# SCH_Rover-Scheme1_2026-06-01.net
KiCad netlist of a schematic drawn in EasyEDA
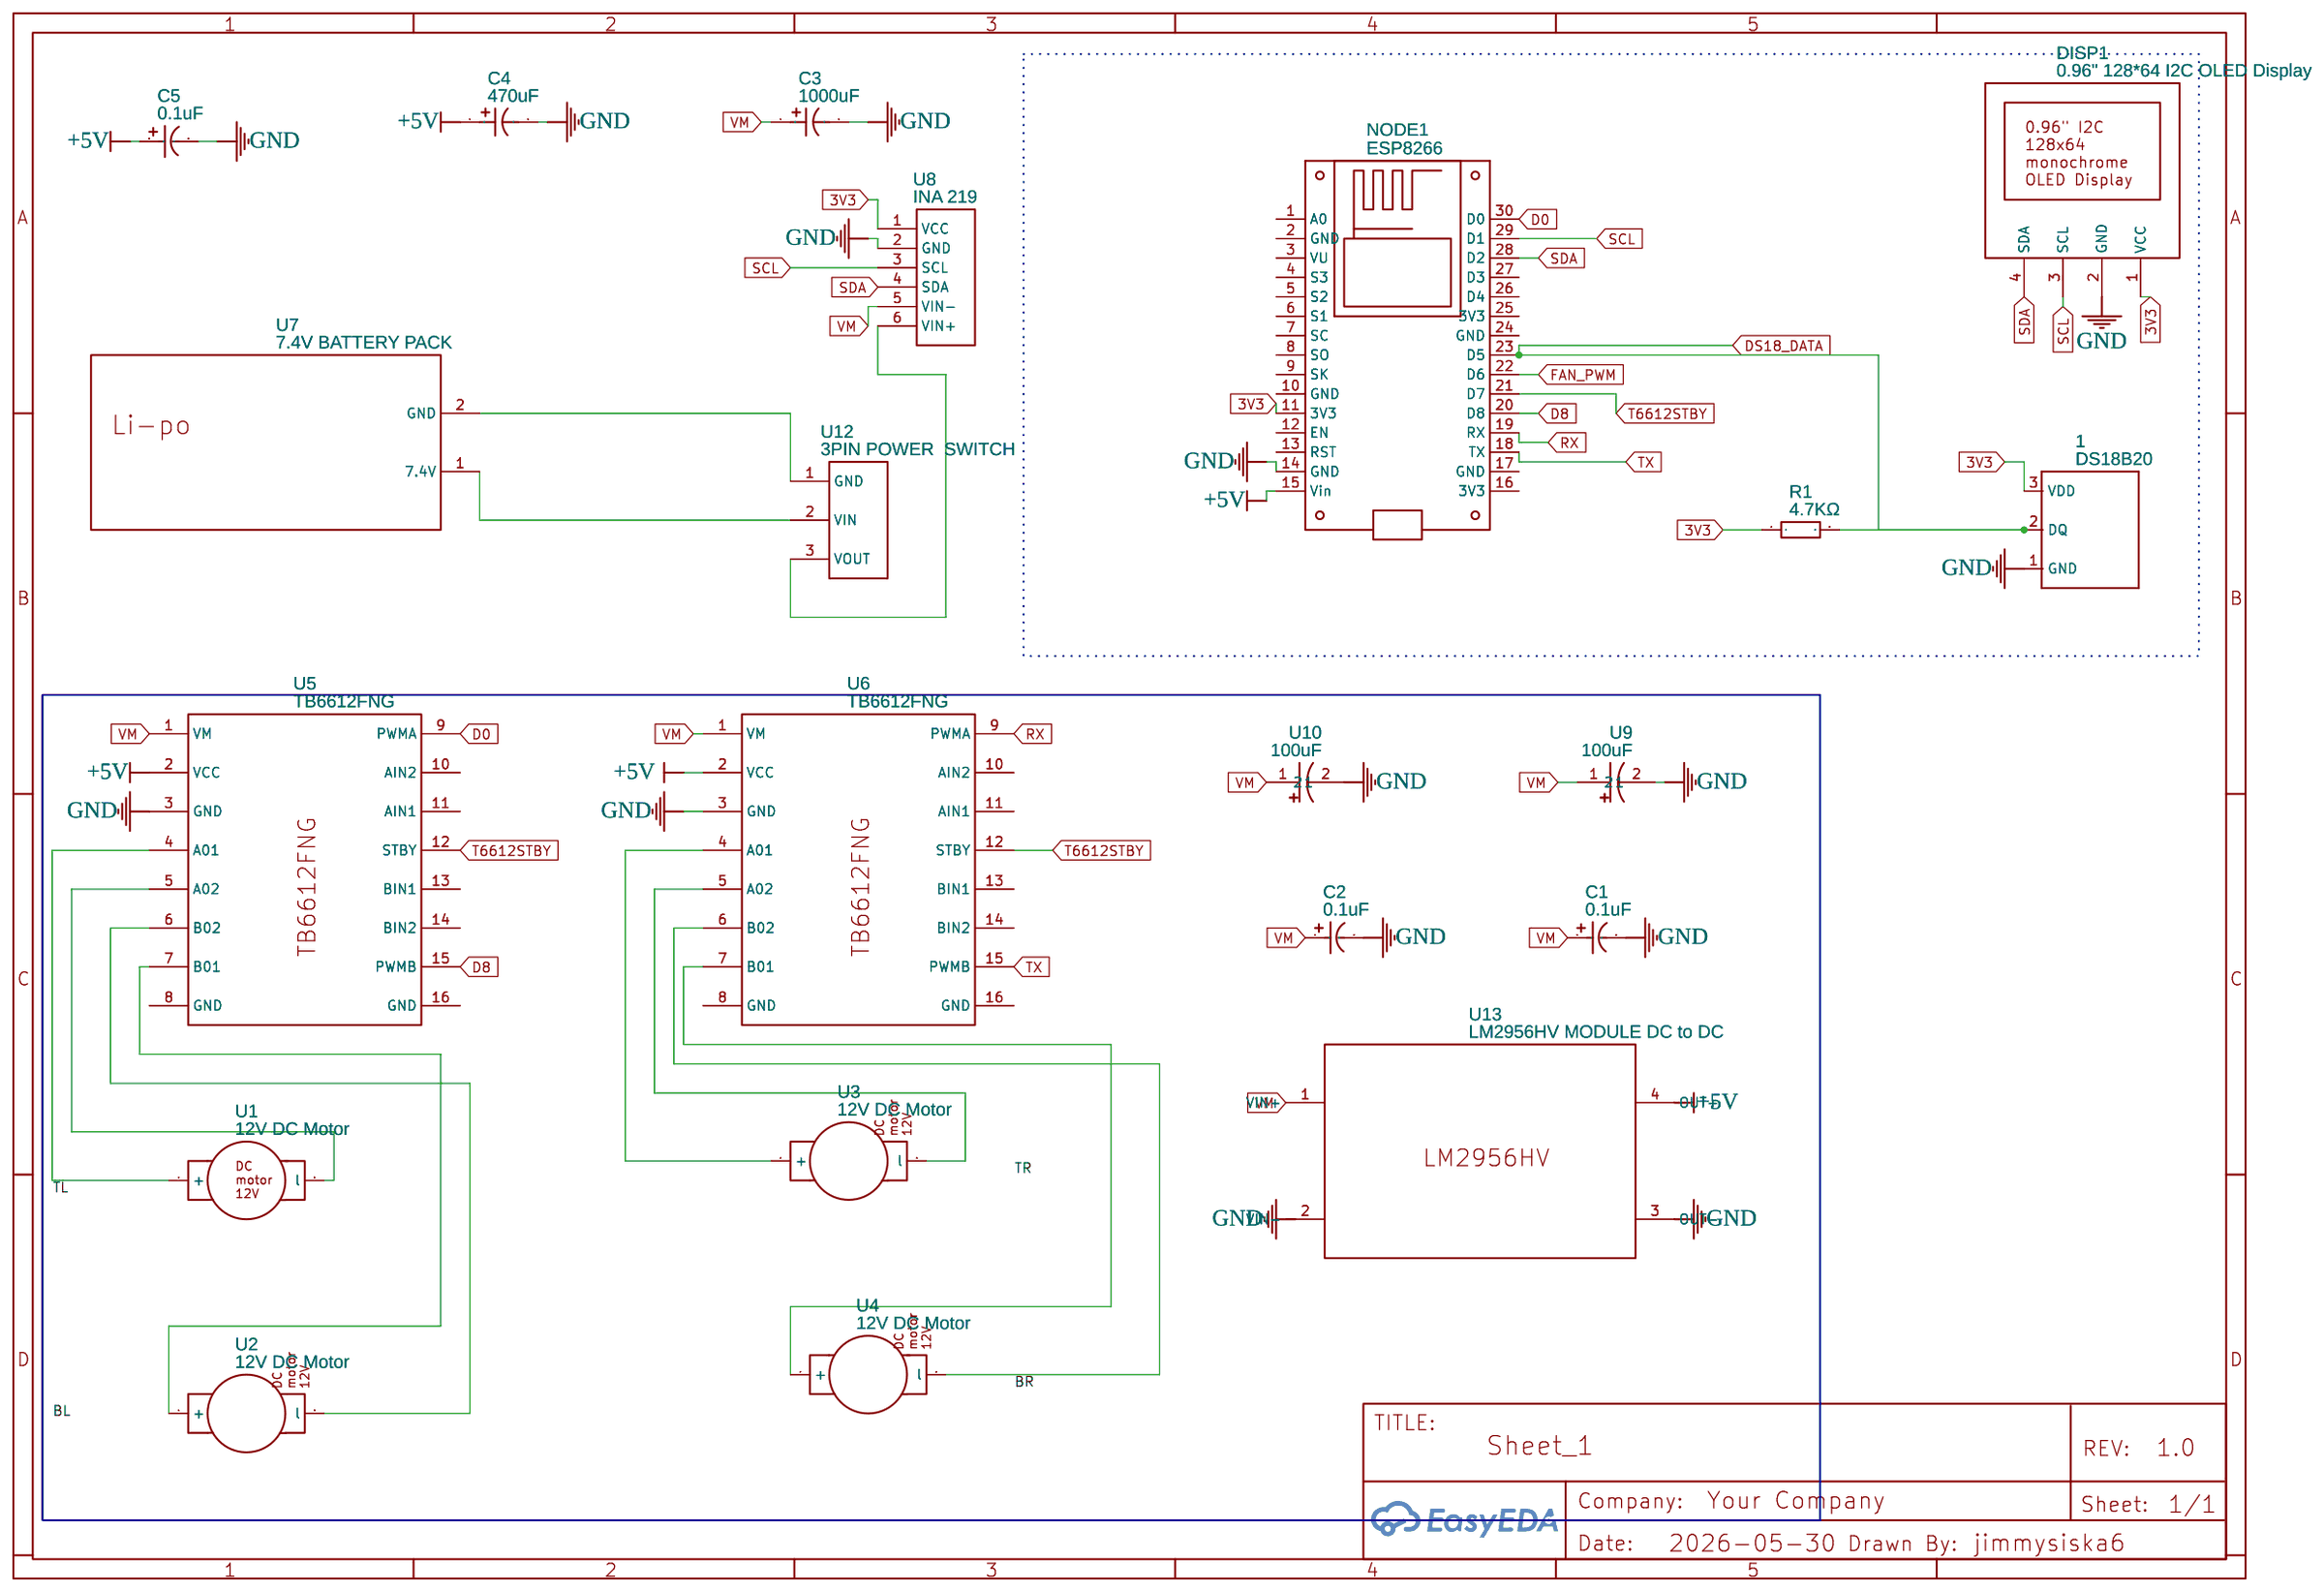
[diagram p0: schematic sheet]

(export (version "E")
  (design (tool "Eeschema 10.0.6"))
  (components
    (comp (ref "1") (value "DS18B20") (libsource (lib "") (part "DS18B20")))
    (comp (ref "C1") (value "0.1uF") (libsource (lib "") (part "0.1uF")))
    (comp (ref "C2") (value "0.1uF") (libsource (lib "") (part "0.1uF")))
    (comp (ref "C3")
      (value "1000uF")
      (fields
        (field (name "Manufacturer Part") "1000uF10V8x14GF")
        (field (name "Manufacturer") "Econd(米朗电子)")
      )
      (libsource (lib "") (part "1000UF10V8X14GF"))
    )
    (comp (ref "C4")
      (value "470uF")
      (fields (field (name "Manufacturer Part") "16V470uF CD288") (field (name "Manufacturer") "HRK(鸿瑞凯电子)"))
      (libsource (lib "") (part "16V470UF CD288"))
    )
    (comp (ref "C5") (value "0.1uF") (libsource (lib "") (part "0.1uF")))
    (comp (ref "DISP1")
      (value "0.96\" 128*64 I2C OLED Display")
      (libsource (lib "") (part "0.96{dblquote} 128*64 I2C OLED Display"))
    )
    (comp (ref "NODE1")
      (value "ESP8266")
      (fields (field (name "Manufacturer Part") "‎3-01-1841") (field (name "Manufacturer") "HiLetgo"))
      (libsource (lib "") (part "NODE MCU V3 ESP8266"))
    )
    (comp (ref "R1")
      (value "4.7KΩ")
      (fields (field (name "Manufacturer Part") "RC0402FR-074K7L") (field (name "Manufacturer") "Yageo"))
      (libsource (lib "") (part "4.7KΩ"))
    )
    (comp (ref "U1") (value "12V DC Motor") (libsource (lib "") (part "12V DC Motor_1")))
    (comp (ref "U2") (value "12V DC Motor") (libsource (lib "") (part "12V DC Motor")))
    (comp (ref "U3") (value "12V DC Motor") (libsource (lib "") (part "12V DC Motor")))
    (comp (ref "U4") (value "12V DC Motor") (libsource (lib "") (part "12V DC Motor")))
    (comp (ref "U5") (value "TB6612FNG") (libsource (lib "") (part "TB6612FNG")))
    (comp (ref "U6") (value "TB6612FNG") (libsource (lib "") (part "TB6612FNG")))
    (comp (ref "U7") (value "7.4V BATTERY PACK") (libsource (lib "") (part "7.2V BATTERY PACK")))
    (comp (ref "U8") (value "INA 219") (libsource (lib "") (part "INA 219")))
    (comp (ref "U9")
      (value "100uF")
      (fields
        (field (name "Manufacturer Part") "6.3NA100MEFC5X11")
        (field (name "Manufacturer") "rubycon(红宝石)")
      )
      (libsource (lib "") (part "100UF-D5XL11MM-HORN-TYPE-POLAR-ELECTROLYTIC-CAPACITORS COPY"))
    )
    (comp (ref "U10")
      (value "100uF")
      (fields
        (field (name "Manufacturer Part") "6.3NA100MEFC5X11")
        (field (name "Manufacturer") "rubycon(红宝石)")
      )
      (libsource (lib "") (part "100UF-D5XL11MM-HORN-TYPE-POLAR-ELECTROLYTIC-CAPACITORS COPY"))
    )
    (comp (ref "U12") (value "3PIN POWER  SWITCH") (libsource (lib "") (part "3PIN POWER  SWITCH")))
    (comp (ref "U13")
      (value "LM2956HV MODULE DC to DC")
      (libsource (lib "") (part "LM2956HV MODULE DC to DC"))
    )
  )
  (nets
    (net (code "1") (name "+5V") (class "Default")
      (node (ref "C4") (pin "1") (pinfunction "1_1") (pintype "input"))
      (node (ref "C5") (pin "1") (pinfunction "1_1") (pintype "input"))
      (node (ref "NODE1") (pin "15") (pinfunction "Vin_15") (pintype "unspecified"))
      (node (ref "U5") (pin "2") (pinfunction "VCC_2") (pintype "unspecified"))
      (node (ref "U6") (pin "2") (pinfunction "VCC_2") (pintype "unspecified"))
    )
    (net (code "6") (name "3V3") (class "Default")
      (node (ref "1") (pin "3") (pinfunction "VDD_3") (pintype "bidirectional"))
      (node (ref "DISP1") (pin "1") (pinfunction "VCC_1") (pintype "unspecified"))
      (node (ref "NODE1") (pin "11") (pinfunction "3V3_11") (pintype "unspecified"))
      (node (ref "R1") (pin "1") (pinfunction "1_1") (pintype "input"))
      (node (ref "U8") (pin "1") (pinfunction "VCC_1") (pintype "unspecified"))
    )
    (net (code "7") (name "D0") (class "Default")
      (node (ref "NODE1") (pin "30") (pinfunction "D0_30") (pintype "unspecified"))
      (node (ref "U5") (pin "9") (pinfunction "PWMA_9") (pintype "unspecified"))
    )
    (net (code "8") (name "D8") (class "Default")
      (node (ref "NODE1") (pin "20") (pinfunction "D8_20") (pintype "unspecified"))
      (node (ref "U5") (pin "15") (pinfunction "PWMB_15") (pintype "unspecified"))
    )
    (net (code "9") (name "DS18_DATA") (class "Default")
      (node (ref "1") (pin "2") (pinfunction "DQ_2") (pintype "bidirectional"))
      (node (ref "NODE1") (pin "23") (pinfunction "D5_23") (pintype "unspecified"))
      (node (ref "R1") (pin "2") (pinfunction "2_2") (pintype "input"))
    )
    (net (code "10") (name "FAN_PWM") (class "Default")
      (node (ref "NODE1") (pin "22") (pinfunction "D6_22") (pintype "unspecified"))
    )
    (net (code "11") (name "GND") (class "Default")
      (node (ref "1") (pin "1") (pinfunction "GND_1") (pintype "bidirectional"))
      (node (ref "C1") (pin "2") (pinfunction "2_2") (pintype "input"))
      (node (ref "C2") (pin "2") (pinfunction "2_2") (pintype "input"))
      (node (ref "C3") (pin "2") (pinfunction "2_2") (pintype "input"))
      (node (ref "C4") (pin "2") (pinfunction "2_2") (pintype "input"))
      (node (ref "C5") (pin "2") (pinfunction "2_2") (pintype "input"))
      (node (ref "DISP1") (pin "2") (pinfunction "GND_2") (pintype "unspecified"))
      (node (ref "NODE1") (pin "14") (pinfunction "GND_14") (pintype "unspecified"))
      (node (ref "U10") (pin "2") (pinfunction "2_2") (pintype "unspecified"))
      (node (ref "U5") (pin "3") (pinfunction "GND_3") (pintype "unspecified"))
      (node (ref "U6") (pin "3") (pinfunction "GND_3") (pintype "unspecified"))
      (node (ref "U8") (pin "2") (pinfunction "GND_2") (pintype "unspecified"))
      (node (ref "U9") (pin "2") (pinfunction "2_2") (pintype "unspecified"))
    )
    (net (code "12") (name "Net-(U1-+)") (class "Default")
      (node (ref "U1") (pin "1") (pinfunction "+_1") (pintype "unspecified"))
      (node (ref "U5") (pin "4") (pinfunction "A01_4") (pintype "unspecified"))
    )
    (net (code "13") (name "Net-(U1-l)") (class "Default")
      (node (ref "U1") (pin "2") (pinfunction "l_2") (pintype "unspecified"))
      (node (ref "U5") (pin "5") (pinfunction "A02_5") (pintype "unspecified"))
    )
    (net (code "14") (name "Net-(U2-+)") (class "Default")
      (node (ref "U2") (pin "1") (pinfunction "+_1") (pintype "unspecified"))
      (node (ref "U5") (pin "7") (pinfunction "B01_7") (pintype "unspecified"))
    )
    (net (code "15") (name "Net-(U2-l)") (class "Default")
      (node (ref "U2") (pin "2") (pinfunction "l_2") (pintype "unspecified"))
      (node (ref "U5") (pin "6") (pinfunction "B02_6") (pintype "unspecified"))
    )
    (net (code "16") (name "Net-(U3-+)") (class "Default")
      (node (ref "U3") (pin "1") (pinfunction "+_1") (pintype "unspecified"))
      (node (ref "U6") (pin "4") (pinfunction "A01_4") (pintype "unspecified"))
    )
    (net (code "17") (name "Net-(U3-l)") (class "Default")
      (node (ref "U3") (pin "2") (pinfunction "l_2") (pintype "unspecified"))
      (node (ref "U6") (pin "5") (pinfunction "A02_5") (pintype "unspecified"))
    )
    (net (code "18") (name "Net-(U4-+)") (class "Default")
      (node (ref "U4") (pin "1") (pinfunction "+_1") (pintype "unspecified"))
      (node (ref "U6") (pin "7") (pinfunction "B01_7") (pintype "unspecified"))
    )
    (net (code "19") (name "Net-(U4-l)") (class "Default")
      (node (ref "U4") (pin "2") (pinfunction "l_2") (pintype "unspecified"))
      (node (ref "U6") (pin "6") (pinfunction "B02_6") (pintype "unspecified"))
    )
    (net (code "20") (name "Net-(U12-GND)") (class "Default")
      (node (ref "U12") (pin "1") (pinfunction "GND_1") (pintype "unspecified"))
      (node (ref "U7") (pin "2") (pinfunction "GND_2") (pintype "unspecified"))
    )
    (net (code "21") (name "Net-(U12-VIN)") (class "Default")
      (node (ref "U12") (pin "2") (pinfunction "VIN_2") (pintype "unspecified"))
      (node (ref "U7") (pin "1") (pinfunction "7.4V_1") (pintype "passive"))
    )
    (net (code "22") (name "Net-(U12-VOUT)") (class "Default")
      (node (ref "U12") (pin "3") (pinfunction "VOUT_3") (pintype "unspecified"))
      (node (ref "U8") (pin "6") (pinfunction "VIN+_6") (pintype "unspecified"))
    )
    (net (code "23") (name "RX") (class "Default")
      (node (ref "NODE1") (pin "19") (pinfunction "RX_19") (pintype "unspecified"))
      (node (ref "U6") (pin "9") (pinfunction "PWMA_9") (pintype "unspecified"))
    )
    (net (code "24") (name "SCL") (class "Default")
      (node (ref "DISP1") (pin "3") (pinfunction "SCL_3") (pintype "unspecified"))
      (node (ref "NODE1") (pin "29") (pinfunction "D1_29") (pintype "unspecified"))
      (node (ref "U8") (pin "3") (pinfunction "SCL_3") (pintype "unspecified"))
    )
    (net (code "25") (name "SDA") (class "Default")
      (node (ref "DISP1") (pin "4") (pinfunction "SDA_4") (pintype "unspecified"))
      (node (ref "NODE1") (pin "28") (pinfunction "D2_28") (pintype "unspecified"))
      (node (ref "U8") (pin "4") (pinfunction "SDA_4") (pintype "unspecified"))
    )
    (net (code "26") (name "T6612STBY") (class "Default")
      (node (ref "NODE1") (pin "21") (pinfunction "D7_21") (pintype "unspecified"))
      (node (ref "U5") (pin "12") (pinfunction "STBY_12") (pintype "unspecified"))
      (node (ref "U6") (pin "12") (pinfunction "STBY_12") (pintype "unspecified"))
    )
    (net (code "27") (name "TX") (class "Default")
      (node (ref "NODE1") (pin "18") (pinfunction "TX_18") (pintype "unspecified"))
      (node (ref "U6") (pin "15") (pinfunction "PWMB_15") (pintype "unspecified"))
    )
    (net (code "28") (name "VM") (class "Default")
      (node (ref "C1") (pin "1") (pinfunction "1_1") (pintype "input"))
      (node (ref "C2") (pin "1") (pinfunction "1_1") (pintype "input"))
      (node (ref "C3") (pin "1") (pinfunction "1_1") (pintype "input"))
      (node (ref "U10") (pin "1") (pinfunction "1_1") (pintype "unspecified"))
      (node (ref "U5") (pin "1") (pinfunction "VM_1") (pintype "unspecified"))
      (node (ref "U6") (pin "1") (pinfunction "VM_1") (pintype "unspecified"))
      (node (ref "U8") (pin "5") (pinfunction "VIN-_5") (pintype "unspecified"))
      (node (ref "U9") (pin "1") (pinfunction "1_1") (pintype "unspecified"))
    )
    (net (code "29") (name "unconnected-(NODE1-3V3-Pad16)") (class "Default")
      (node (ref "NODE1") (pin "16") (pinfunction "3V3_16") (pintype "unspecified"))
    )
    (net (code "30") (name "unconnected-(NODE1-3V3-Pad25)") (class "Default")
      (node (ref "NODE1") (pin "25") (pinfunction "3V3_25") (pintype "unspecified"))
    )
    (net (code "31") (name "unconnected-(NODE1-A0-Pad1)") (class "Default")
      (node (ref "NODE1") (pin "1") (pinfunction "A0_1") (pintype "unspecified"))
    )
    (net (code "32") (name "unconnected-(NODE1-D3-Pad27)") (class "Default")
      (node (ref "NODE1") (pin "27") (pinfunction "D3_27") (pintype "unspecified"))
    )
    (net (code "33") (name "unconnected-(NODE1-D4-Pad26)") (class "Default")
      (node (ref "NODE1") (pin "26") (pinfunction "D4_26") (pintype "unspecified"))
    )
    (net (code "34") (name "unconnected-(NODE1-EN-Pad12)") (class "Default")
      (node (ref "NODE1") (pin "12") (pinfunction "EN_12") (pintype "unspecified"))
    )
    (net (code "35") (name "unconnected-(NODE1-GND-Pad2)") (class "Default")
      (node (ref "NODE1") (pin "2") (pinfunction "GND_2") (pintype "unspecified"))
    )
    (net (code "36") (name "unconnected-(NODE1-GND-Pad10)") (class "Default")
      (node (ref "NODE1") (pin "10") (pinfunction "GND_10") (pintype "unspecified"))
    )
    (net (code "37") (name "unconnected-(NODE1-GND-Pad17)") (class "Default")
      (node (ref "NODE1") (pin "17") (pinfunction "GND_17") (pintype "unspecified"))
    )
    (net (code "38") (name "unconnected-(NODE1-GND-Pad24)") (class "Default")
      (node (ref "NODE1") (pin "24") (pinfunction "GND_24") (pintype "unspecified"))
    )
    (net (code "39") (name "unconnected-(NODE1-RST-Pad13)") (class "Default")
      (node (ref "NODE1") (pin "13") (pinfunction "RST_13") (pintype "unspecified"))
    )
    (net (code "40") (name "unconnected-(NODE1-S1-Pad6)") (class "Default")
      (node (ref "NODE1") (pin "6") (pinfunction "S1_6") (pintype "unspecified"))
    )
    (net (code "41") (name "unconnected-(NODE1-S2-Pad5)") (class "Default")
      (node (ref "NODE1") (pin "5") (pinfunction "S2_5") (pintype "unspecified"))
    )
    (net (code "42") (name "unconnected-(NODE1-S3-Pad4)") (class "Default")
      (node (ref "NODE1") (pin "4") (pinfunction "S3_4") (pintype "unspecified"))
    )
    (net (code "43") (name "unconnected-(NODE1-SC-Pad7)") (class "Default")
      (node (ref "NODE1") (pin "7") (pinfunction "SC_7") (pintype "unspecified"))
    )
    (net (code "44") (name "unconnected-(NODE1-SK-Pad9)") (class "Default")
      (node (ref "NODE1") (pin "9") (pinfunction "SK_9") (pintype "unspecified"))
    )
    (net (code "45") (name "unconnected-(NODE1-SO-Pad8)") (class "Default")
      (node (ref "NODE1") (pin "8") (pinfunction "SO_8") (pintype "unspecified"))
    )
    (net (code "46") (name "unconnected-(NODE1-VU-Pad3)") (class "Default")
      (node (ref "NODE1") (pin "3") (pinfunction "VU_3") (pintype "unspecified"))
    )
    (net (code "47") (name "unconnected-(U5-AIN1-Pad11)") (class "Default")
      (node (ref "U5") (pin "11") (pinfunction "AIN1_11") (pintype "unspecified"))
    )
    (net (code "48") (name "unconnected-(U5-AIN2-Pad10)") (class "Default")
      (node (ref "U5") (pin "10") (pinfunction "AIN2_10") (pintype "unspecified"))
    )
    (net (code "49") (name "unconnected-(U5-BIN1-Pad13)") (class "Default")
      (node (ref "U5") (pin "13") (pinfunction "BIN1_13") (pintype "unspecified"))
    )
    (net (code "50") (name "unconnected-(U5-BIN2-Pad14)") (class "Default")
      (node (ref "U5") (pin "14") (pinfunction "BIN2_14") (pintype "unspecified"))
    )
    (net (code "51") (name "unconnected-(U5-GND-Pad8)") (class "Default")
      (node (ref "U5") (pin "8") (pinfunction "GND_8") (pintype "unspecified"))
    )
    (net (code "52") (name "unconnected-(U5-GND-Pad16)") (class "Default")
      (node (ref "U5") (pin "16") (pinfunction "GND_16") (pintype "unspecified"))
    )
    (net (code "53") (name "unconnected-(U6-AIN1-Pad11)") (class "Default")
      (node (ref "U6") (pin "11") (pinfunction "AIN1_11") (pintype "unspecified"))
    )
    (net (code "54") (name "unconnected-(U6-AIN2-Pad10)") (class "Default")
      (node (ref "U6") (pin "10") (pinfunction "AIN2_10") (pintype "unspecified"))
    )
    (net (code "55") (name "unconnected-(U6-BIN1-Pad13)") (class "Default")
      (node (ref "U6") (pin "13") (pinfunction "BIN1_13") (pintype "unspecified"))
    )
    (net (code "56") (name "unconnected-(U6-BIN2-Pad14)") (class "Default")
      (node (ref "U6") (pin "14") (pinfunction "BIN2_14") (pintype "unspecified"))
    )
    (net (code "57") (name "unconnected-(U6-GND-Pad8)") (class "Default")
      (node (ref "U6") (pin "8") (pinfunction "GND_8") (pintype "unspecified"))
    )
    (net (code "58") (name "unconnected-(U6-GND-Pad16)") (class "Default")
      (node (ref "U6") (pin "16") (pinfunction "GND_16") (pintype "unspecified"))
    )
    (net (code "59") (name "unconnected-(U13-OUT+-Pad4)") (class "Default")
      (node (ref "U13") (pin "4") (pinfunction "OUT+_4") (pintype "unspecified"))
    )
    (net (code "60") (name "unconnected-(U13-OUT--Pad3)") (class "Default")
      (node (ref "U13") (pin "3") (pinfunction "OUT-_3") (pintype "unspecified"))
    )
    (net (code "61") (name "unconnected-(U13-VIN+-Pad1)") (class "Default")
      (node (ref "U13") (pin "1") (pinfunction "VIN+_1") (pintype "unspecified"))
    )
    (net (code "62") (name "unconnected-(U13-VIN--Pad2)") (class "Default")
      (node (ref "U13") (pin "2") (pinfunction "VIN-_2") (pintype "unspecified"))
    )
  )
)
